# main_v2.net
KiCad netlist of a schematic drawn in EAGLE
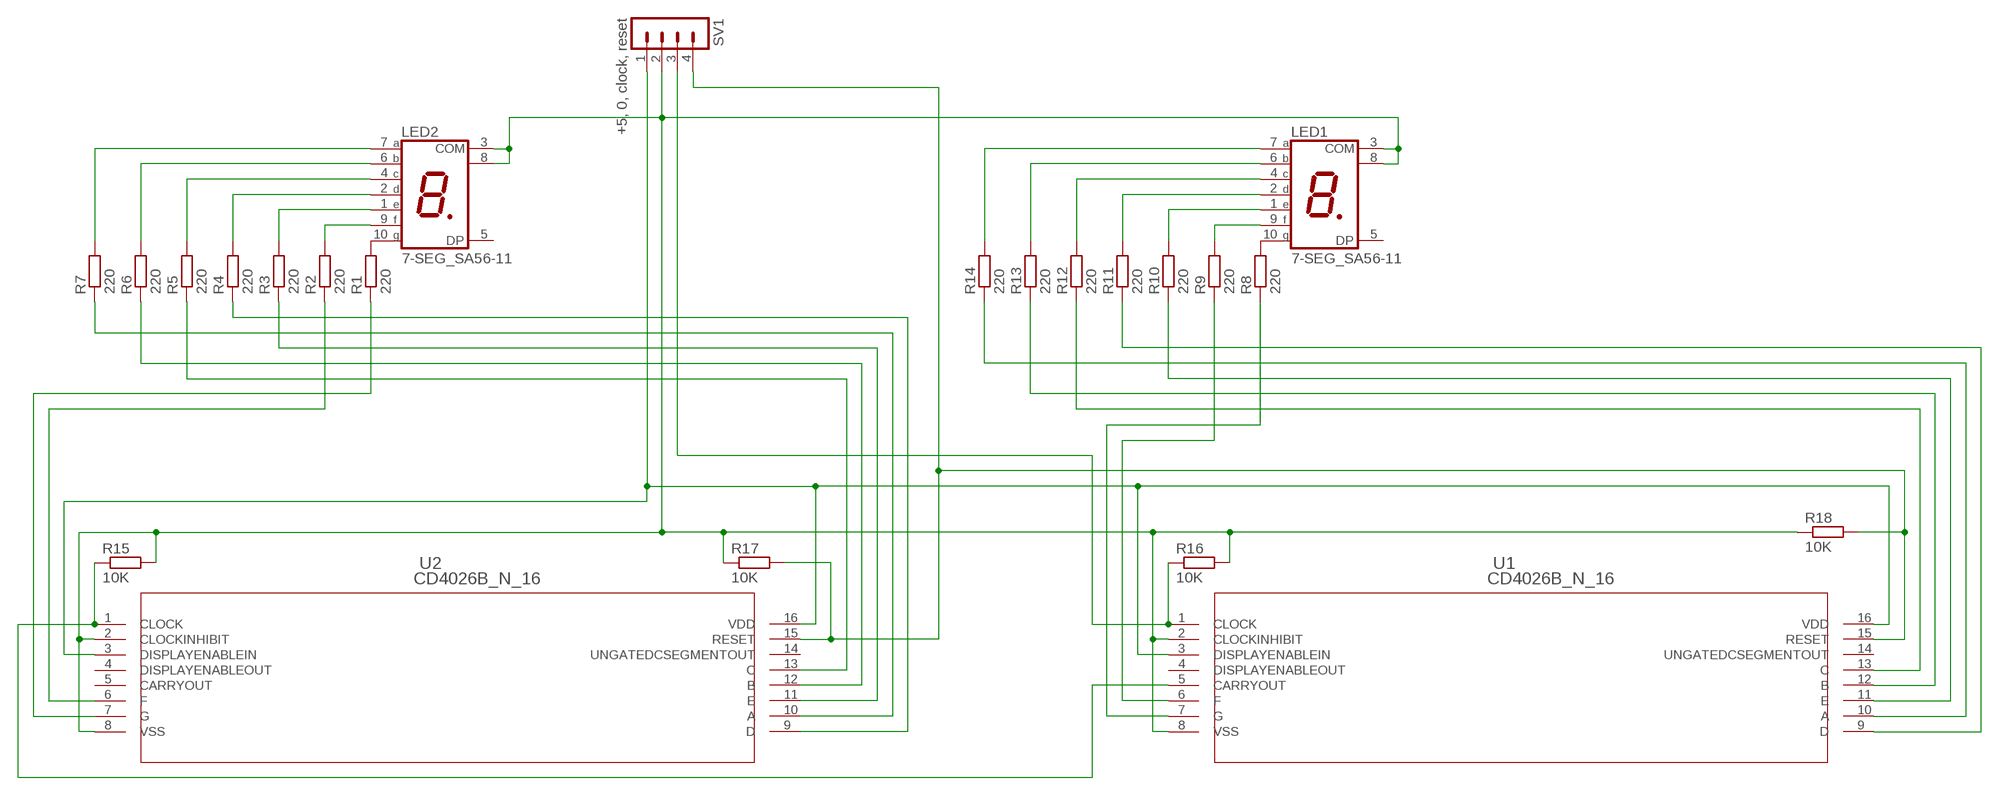
[diagram p0: schematic, sheet 1]

(export (version "E")
  (design (tool "Eeschema 10.0.6"))
  (components
    (comp (ref "LED1")
      (value "7-SEG_SA56-11")
      (footprint "eagle-import:SA56-11")
      (libsource (lib "eagle-import") (part "7-SEG_SA56-11"))
    )
    (comp (ref "LED2")
      (value "7-SEG_SA56-11")
      (footprint "eagle-import:SA56-11")
      (libsource (lib "eagle-import") (part "7-SEG_SA56-11"))
    )
    (comp (ref "R1")
      (value "220")
      (footprint "eagle-import:R0805")
      (libsource (lib "eagle-import") (part "R-EU_R0805"))
    )
    (comp (ref "R2")
      (value "220")
      (footprint "eagle-import:R0805")
      (libsource (lib "eagle-import") (part "R-EU_R0805"))
    )
    (comp (ref "R3")
      (value "220")
      (footprint "eagle-import:R0805")
      (libsource (lib "eagle-import") (part "R-EU_R0805"))
    )
    (comp (ref "R4")
      (value "220")
      (footprint "eagle-import:R0805")
      (libsource (lib "eagle-import") (part "R-EU_R0805"))
    )
    (comp (ref "R5")
      (value "220")
      (footprint "eagle-import:R0805")
      (libsource (lib "eagle-import") (part "R-EU_R0805"))
    )
    (comp (ref "R6")
      (value "220")
      (footprint "eagle-import:R0805")
      (libsource (lib "eagle-import") (part "R-EU_R0805"))
    )
    (comp (ref "R7")
      (value "220")
      (footprint "eagle-import:R0805")
      (libsource (lib "eagle-import") (part "R-EU_R0805"))
    )
    (comp (ref "R8")
      (value "220")
      (footprint "eagle-import:R0805")
      (libsource (lib "eagle-import") (part "R-EU_R0805"))
    )
    (comp (ref "R9")
      (value "220")
      (footprint "eagle-import:R0805")
      (libsource (lib "eagle-import") (part "R-EU_R0805"))
    )
    (comp (ref "R10")
      (value "220")
      (footprint "eagle-import:R0805")
      (libsource (lib "eagle-import") (part "R-EU_R0805"))
    )
    (comp (ref "R11")
      (value "220")
      (footprint "eagle-import:R0805")
      (libsource (lib "eagle-import") (part "R-EU_R0805"))
    )
    (comp (ref "R12")
      (value "220")
      (footprint "eagle-import:R0805")
      (libsource (lib "eagle-import") (part "R-EU_R0805"))
    )
    (comp (ref "R13")
      (value "220")
      (footprint "eagle-import:R0805")
      (libsource (lib "eagle-import") (part "R-EU_R0805"))
    )
    (comp (ref "R14")
      (value "220")
      (footprint "eagle-import:R0805")
      (libsource (lib "eagle-import") (part "R-EU_R0805"))
    )
    (comp (ref "R15")
      (value "10K")
      (footprint "eagle-import:R0805")
      (libsource (lib "eagle-import") (part "R-EU_R0805"))
    )
    (comp (ref "R16")
      (value "10K")
      (footprint "eagle-import:R0805")
      (libsource (lib "eagle-import") (part "R-EU_R0805"))
    )
    (comp (ref "R17")
      (value "10K")
      (footprint "eagle-import:R0805")
      (libsource (lib "eagle-import") (part "R-EU_R0805"))
    )
    (comp (ref "R18")
      (value "10K")
      (footprint "eagle-import:R0805")
      (libsource (lib "eagle-import") (part "R-EU_R0805"))
    )
    (comp (ref "SV1")
      (value "+5, 0, clock, reset")
      (footprint "eagle-import:MA04-1")
      (libsource (lib "eagle-import") (part "MA04-1"))
    )
    (comp (ref "U1")
      (value "CD4026B_N_16")
      (footprint "eagle-import:N16")
      (fields
        (field (name "GENERIC_PART_NUMBER") "CD4026B")
        (field (name "MANUFACTURER") "Texas Instruments")
      )
      (libsource (lib "eagle-import") (part "CD4026B_N_16"))
    )
    (comp (ref "U2")
      (value "CD4026B_N_16")
      (footprint "eagle-import:N16")
      (fields
        (field (name "GENERIC_PART_NUMBER") "CD4026B")
        (field (name "MANUFACTURER") "Texas Instruments")
      )
      (libsource (lib "eagle-import") (part "CD4026B_N_16"))
    )
  )
  (nets
    (net (code "1") (name "Net-(LED1-A)") (class "Default")
      (node (ref "LED1") (pin "7") (pinfunction "A_7") (pintype "passive"))
      (node (ref "R14") (pin "2") (pinfunction "2_2") (pintype "passive"))
    )
    (net (code "2") (name "Net-(LED1-B)") (class "Default")
      (node (ref "LED1") (pin "6") (pinfunction "B_6") (pintype "passive"))
      (node (ref "R13") (pin "2") (pinfunction "2_2") (pintype "passive"))
    )
    (net (code "3") (name "Net-(LED1-C)") (class "Default")
      (node (ref "LED1") (pin "4") (pinfunction "C_4") (pintype "passive"))
      (node (ref "R12") (pin "2") (pinfunction "2_2") (pintype "passive"))
    )
    (net (code "4") (name "Net-(LED1-D)") (class "Default")
      (node (ref "LED1") (pin "2") (pinfunction "D_2") (pintype "passive"))
      (node (ref "R11") (pin "2") (pinfunction "2_2") (pintype "passive"))
    )
    (net (code "5") (name "Net-(LED1-E)") (class "Default")
      (node (ref "LED1") (pin "1") (pinfunction "E_1") (pintype "passive"))
      (node (ref "R10") (pin "2") (pinfunction "2_2") (pintype "passive"))
    )
    (net (code "6") (name "Net-(LED1-F)") (class "Default")
      (node (ref "LED1") (pin "9") (pinfunction "F_9") (pintype "passive"))
      (node (ref "R9") (pin "2") (pinfunction "2_2") (pintype "passive"))
    )
    (net (code "7") (name "Net-(LED1-G)") (class "Default")
      (node (ref "LED1") (pin "10") (pinfunction "G_10") (pintype "passive"))
      (node (ref "R8") (pin "2") (pinfunction "2_2") (pintype "passive"))
    )
    (net (code "8") (name "Net-(LED2-A)") (class "Default")
      (node (ref "LED2") (pin "7") (pinfunction "A_7") (pintype "passive"))
      (node (ref "R7") (pin "2") (pinfunction "2_2") (pintype "passive"))
    )
    (net (code "9") (name "Net-(LED2-B)") (class "Default")
      (node (ref "LED2") (pin "6") (pinfunction "B_6") (pintype "passive"))
      (node (ref "R6") (pin "2") (pinfunction "2_2") (pintype "passive"))
    )
    (net (code "10") (name "Net-(LED2-C)") (class "Default")
      (node (ref "LED2") (pin "4") (pinfunction "C_4") (pintype "passive"))
      (node (ref "R5") (pin "2") (pinfunction "2_2") (pintype "passive"))
    )
    (net (code "11") (name "Net-(LED2-D)") (class "Default")
      (node (ref "LED2") (pin "2") (pinfunction "D_2") (pintype "passive"))
      (node (ref "R4") (pin "2") (pinfunction "2_2") (pintype "passive"))
    )
    (net (code "12") (name "Net-(LED2-E)") (class "Default")
      (node (ref "LED2") (pin "1") (pinfunction "E_1") (pintype "passive"))
      (node (ref "R3") (pin "2") (pinfunction "2_2") (pintype "passive"))
    )
    (net (code "13") (name "Net-(LED2-F)") (class "Default")
      (node (ref "LED2") (pin "9") (pinfunction "F_9") (pintype "passive"))
      (node (ref "R2") (pin "2") (pinfunction "2_2") (pintype "passive"))
    )
    (net (code "14") (name "Net-(LED2-G)") (class "Default")
      (node (ref "LED2") (pin "10") (pinfunction "G_10") (pintype "passive"))
      (node (ref "R1") (pin "2") (pinfunction "2_2") (pintype "passive"))
    )
    (net (code "15") (name "Net-(U1-A)") (class "Default")
      (node (ref "R14") (pin "1") (pinfunction "1_1") (pintype "passive"))
      (node (ref "U1") (pin "10") (pinfunction "A_10") (pintype "passive"))
    )
    (net (code "16") (name "Net-(U1-B)") (class "Default")
      (node (ref "R13") (pin "1") (pinfunction "1_1") (pintype "passive"))
      (node (ref "U1") (pin "12") (pinfunction "B_12") (pintype "passive"))
    )
    (net (code "17") (name "Net-(U1-C)") (class "Default")
      (node (ref "R12") (pin "1") (pinfunction "1_1") (pintype "passive"))
      (node (ref "U1") (pin "13") (pinfunction "C_13") (pintype "passive"))
    )
    (net (code "18") (name "Net-(U1-CARRYOUT)") (class "Default")
      (node (ref "R15") (pin "1") (pinfunction "1_1") (pintype "passive"))
      (node (ref "U1") (pin "5") (pinfunction "CARRYOUT_5") (pintype "output"))
      (node (ref "U2") (pin "1") (pinfunction "CLOCK_1") (pintype "passive"))
    )
    (net (code "19") (name "Net-(U1-CLOCK)") (class "Default")
      (node (ref "R16") (pin "1") (pinfunction "1_1") (pintype "passive"))
      (node (ref "SV1") (pin "3") (pinfunction "3_3") (pintype "passive"))
      (node (ref "U1") (pin "1") (pinfunction "CLOCK_1") (pintype "passive"))
    )
    (net (code "20") (name "Net-(U1-CLOCKINHIBIT)") (class "Default")
      (node (ref "LED1") (pin "3") (pinfunction "COM_3") (pintype "passive"))
      (node (ref "LED1") (pin "8") (pinfunction "COM_8") (pintype "passive"))
      (node (ref "LED2") (pin "3") (pinfunction "COM_3") (pintype "passive"))
      (node (ref "LED2") (pin "8") (pinfunction "COM_8") (pintype "passive"))
      (node (ref "R15") (pin "2") (pinfunction "2_2") (pintype "passive"))
      (node (ref "R16") (pin "2") (pinfunction "2_2") (pintype "passive"))
      (node (ref "R17") (pin "1") (pinfunction "1_1") (pintype "passive"))
      (node (ref "R18") (pin "1") (pinfunction "1_1") (pintype "passive"))
      (node (ref "SV1") (pin "2") (pinfunction "2_2") (pintype "passive"))
      (node (ref "U1") (pin "2") (pinfunction "CLOCKINHIBIT_2") (pintype "passive"))
      (node (ref "U1") (pin "8") (pinfunction "VSS_8") (pintype "power_in"))
      (node (ref "U2") (pin "2") (pinfunction "CLOCKINHIBIT_2") (pintype "passive"))
      (node (ref "U2") (pin "8") (pinfunction "VSS_8") (pintype "power_in"))
    )
    (net (code "21") (name "Net-(U1-D)") (class "Default")
      (node (ref "R11") (pin "1") (pinfunction "1_1") (pintype "passive"))
      (node (ref "U1") (pin "9") (pinfunction "D_9") (pintype "passive"))
    )
    (net (code "22") (name "Net-(U1-DISPLAYENABLEIN)") (class "Default")
      (node (ref "SV1") (pin "1") (pinfunction "1_1") (pintype "passive"))
      (node (ref "U1") (pin "16") (pinfunction "VDD_16") (pintype "power_in"))
      (node (ref "U1") (pin "3") (pinfunction "DISPLAYENABLEIN_3") (pintype "input"))
      (node (ref "U2") (pin "16") (pinfunction "VDD_16") (pintype "power_in"))
      (node (ref "U2") (pin "3") (pinfunction "DISPLAYENABLEIN_3") (pintype "input"))
    )
    (net (code "23") (name "Net-(U1-E)") (class "Default")
      (node (ref "R10") (pin "1") (pinfunction "1_1") (pintype "passive"))
      (node (ref "U1") (pin "11") (pinfunction "E_11") (pintype "passive"))
    )
    (net (code "24") (name "Net-(U1-F)") (class "Default")
      (node (ref "R9") (pin "1") (pinfunction "1_1") (pintype "passive"))
      (node (ref "U1") (pin "6") (pinfunction "F_6") (pintype "passive"))
    )
    (net (code "25") (name "Net-(U1-G)") (class "Default")
      (node (ref "R8") (pin "1") (pinfunction "1_1") (pintype "passive"))
      (node (ref "U1") (pin "7") (pinfunction "G_7") (pintype "passive"))
    )
    (net (code "26") (name "Net-(U1-RESET)") (class "Default")
      (node (ref "R17") (pin "2") (pinfunction "2_2") (pintype "passive"))
      (node (ref "R18") (pin "2") (pinfunction "2_2") (pintype "passive"))
      (node (ref "SV1") (pin "4") (pinfunction "4_4") (pintype "passive"))
      (node (ref "U1") (pin "15") (pinfunction "RESET_15") (pintype "passive"))
      (node (ref "U2") (pin "15") (pinfunction "RESET_15") (pintype "passive"))
    )
    (net (code "27") (name "Net-(U2-A)") (class "Default")
      (node (ref "R7") (pin "1") (pinfunction "1_1") (pintype "passive"))
      (node (ref "U2") (pin "10") (pinfunction "A_10") (pintype "passive"))
    )
    (net (code "28") (name "Net-(U2-B)") (class "Default")
      (node (ref "R6") (pin "1") (pinfunction "1_1") (pintype "passive"))
      (node (ref "U2") (pin "12") (pinfunction "B_12") (pintype "passive"))
    )
    (net (code "29") (name "Net-(U2-C)") (class "Default")
      (node (ref "R5") (pin "1") (pinfunction "1_1") (pintype "passive"))
      (node (ref "U2") (pin "13") (pinfunction "C_13") (pintype "passive"))
    )
    (net (code "30") (name "Net-(U2-D)") (class "Default")
      (node (ref "R4") (pin "1") (pinfunction "1_1") (pintype "passive"))
      (node (ref "U2") (pin "9") (pinfunction "D_9") (pintype "passive"))
    )
    (net (code "31") (name "Net-(U2-E)") (class "Default")
      (node (ref "R3") (pin "1") (pinfunction "1_1") (pintype "passive"))
      (node (ref "U2") (pin "11") (pinfunction "E_11") (pintype "passive"))
    )
    (net (code "32") (name "Net-(U2-F)") (class "Default")
      (node (ref "R2") (pin "1") (pinfunction "1_1") (pintype "passive"))
      (node (ref "U2") (pin "6") (pinfunction "F_6") (pintype "passive"))
    )
    (net (code "33") (name "Net-(U2-G)") (class "Default")
      (node (ref "R1") (pin "1") (pinfunction "1_1") (pintype "passive"))
      (node (ref "U2") (pin "7") (pinfunction "G_7") (pintype "passive"))
    )
    (net (code "34") (name "unconnected-(LED1-DP-Pad5)") (class "Default")
      (node (ref "LED1") (pin "5") (pinfunction "DP_5") (pintype "passive"))
    )
    (net (code "35") (name "unconnected-(LED2-DP-Pad5)") (class "Default")
      (node (ref "LED2") (pin "5") (pinfunction "DP_5") (pintype "passive"))
    )
    (net (code "36") (name "unconnected-(U1-DISPLAYENABLEOUT-Pad4)") (class "Default")
      (node (ref "U1") (pin "4") (pinfunction "DISPLAYENABLEOUT_4") (pintype "output"))
    )
    (net (code "37") (name "unconnected-(U1-UNGATEDCSEGMENTOUT-Pad14)") (class "Default")
      (node (ref "U1") (pin "14") (pinfunction "UNGATEDCSEGMENTOUT_14") (pintype "output"))
    )
    (net (code "38") (name "unconnected-(U2-CARRYOUT-Pad5)") (class "Default")
      (node (ref "U2") (pin "5") (pinfunction "CARRYOUT_5") (pintype "output"))
    )
    (net (code "39") (name "unconnected-(U2-DISPLAYENABLEOUT-Pad4)") (class "Default")
      (node (ref "U2") (pin "4") (pinfunction "DISPLAYENABLEOUT_4") (pintype "output"))
    )
    (net (code "40") (name "unconnected-(U2-UNGATEDCSEGMENTOUT-Pad14)") (class "Default")
      (node (ref "U2") (pin "14") (pinfunction "UNGATEDCSEGMENTOUT_14") (pintype "output"))
    )
  )
)
